# CEF_JFET.net
KiCad netlist of a schematic drawn in Altium Designer
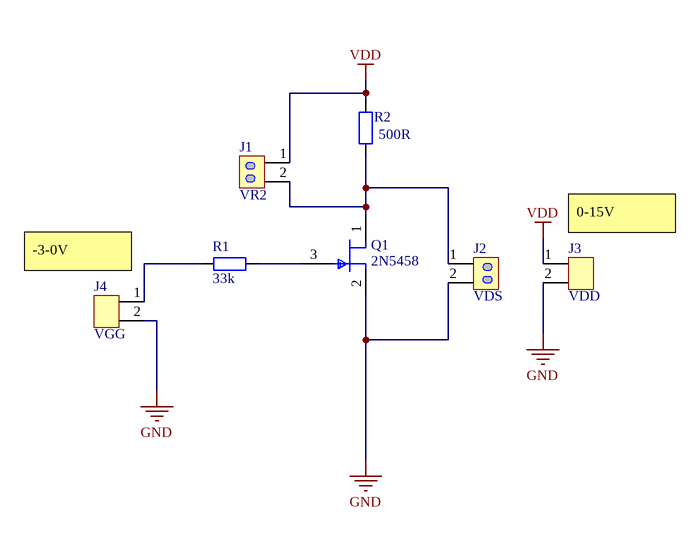
[diagram p0: CEF JFET.SchDoc]

(export (version "E")
  (design (tool "Eeschema 10.0.6"))
  (components
    (comp (ref "J1")
      (value "VR2")
      (footprint "HDR_1x2_pin")
      (description "Header, 2-Pin")
      (libsource (lib "CEF") (part "HDR_1x2"))
    )
    (comp (ref "J2")
      (value "VDS")
      (footprint "HDR_1x2_pin")
      (description "Header, 2-Pin")
      (libsource (lib "") (part "HDR_1x2_1"))
    )
    (comp (ref "J3")
      (value "VDD")
      (footprint "HDR_1X2_TE")
      (description "Connector, 2-Ports")
      (libsource (lib "CEF") (part "CON_1x2"))
    )
    (comp (ref "J4")
      (value "VGG")
      (footprint "HDR_1X2_TE")
      (description "Connector, 2-Ports")
      (libsource (lib "") (part "CON_1x2_1"))
    )
    (comp (ref "Q1")
      (value "2N5458")
      (footprint "FP-29-11-MFG")
      (libsource (lib "Altium Content Vault") (part "2fe1325ee7984bd9864bb4197617735"))
    )
    (comp (ref "R1")
      (value "33k")
      (footprint "Resistor")
      (description "0.25W,Axial")
      (libsource (lib "CEF") (part "Resistor 0.25W 5mm"))
    )
    (comp (ref "R2")
      (value "500R")
      (footprint "Resistor")
      (description "0.25W,Axial")
      (libsource (lib "CEF") (part "Resistor 0.25W 5mm"))
    )
  )
  (nets
    (net (code "1") (name "GND") (class "Default")
      (node (ref "J2") (pin "2") (pinfunction "2_2") (pintype "passive"))
      (node (ref "J3") (pin "2") (pinfunction "2_2") (pintype "passive"))
      (node (ref "J4") (pin "2") (pinfunction "2_2") (pintype "passive"))
      (node (ref "Q1") (pin "2") (pinfunction "SOURCE_2") (pintype "passive"))
    )
    (net (code "2") (name "Net-(J4-Pad1)") (class "Default")
      (node (ref "J4") (pin "1") (pinfunction "1_1") (pintype "passive"))
      (node (ref "R1") (pin "1") (pinfunction "1_1") (pintype "passive"))
    )
    (net (code "3") (name "Net-(Q1-DRAIN)") (class "Default")
      (node (ref "J1") (pin "2") (pinfunction "2_2") (pintype "passive"))
      (node (ref "J2") (pin "1") (pinfunction "1_1") (pintype "passive"))
      (node (ref "Q1") (pin "1") (pinfunction "DRAIN_1") (pintype "passive"))
      (node (ref "R2") (pin "1") (pinfunction "1_1") (pintype "passive"))
    )
    (net (code "4") (name "Net-(Q1-GATE)") (class "Default")
      (node (ref "Q1") (pin "3") (pinfunction "GATE_3") (pintype "passive"))
      (node (ref "R1") (pin "2") (pinfunction "2_2") (pintype "passive"))
    )
    (net (code "5") (name "VDD") (class "Default")
      (node (ref "J1") (pin "1") (pinfunction "1_1") (pintype "passive"))
      (node (ref "J3") (pin "1") (pinfunction "1_1") (pintype "passive"))
      (node (ref "R2") (pin "2") (pinfunction "2_2") (pintype "passive"))
    )
  )
)
